# NMEA-v8-iso.net
KiCad netlist of a schematic drawn in EAGLE
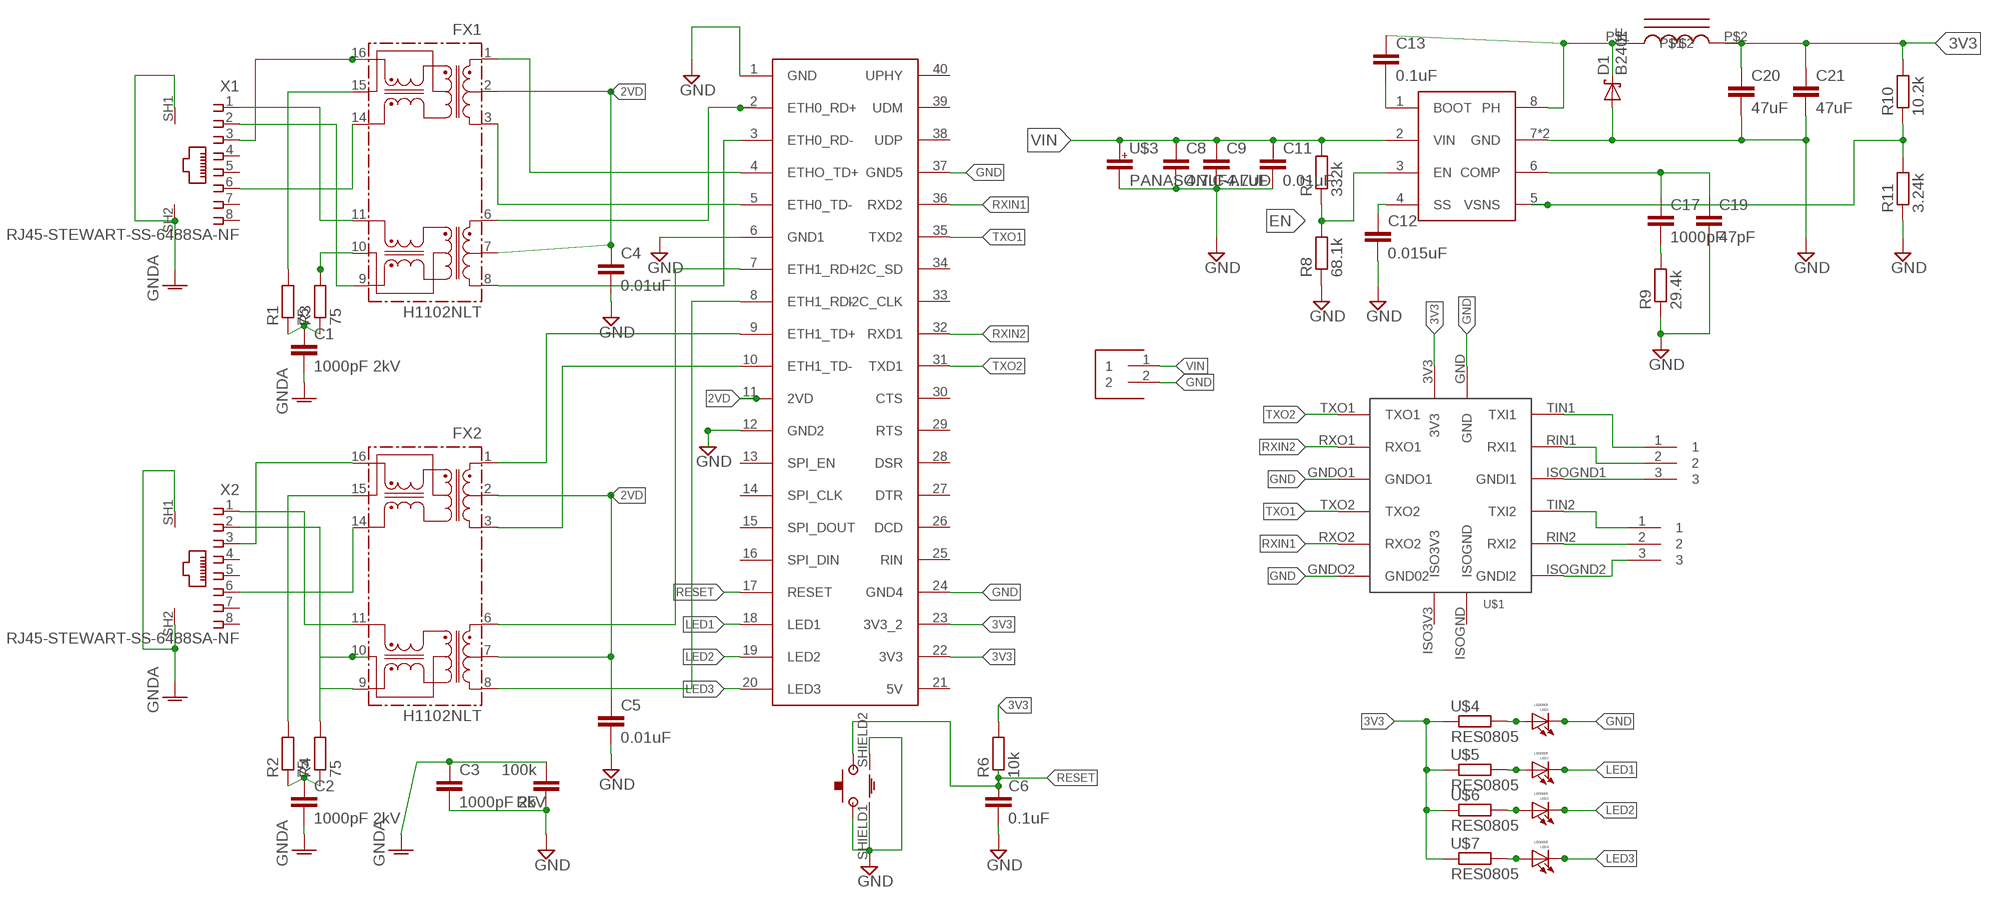
[diagram p0: schematic, sheet 1]

(export (version "E")
  (design (tool "Eeschema 10.0.6"))
  (components
    (comp (ref "C1")
      (value "1000pF 2kV")
      (footprint "eagle-import:1206")
      (libsource (lib "eagle-import") (part "CAP1206"))
    )
    (comp (ref "C2")
      (value "1000pF 2kV")
      (footprint "eagle-import:1206")
      (libsource (lib "eagle-import") (part "CAP1206"))
    )
    (comp (ref "C3")
      (value "1000pF 2kV")
      (footprint "eagle-import:1206")
      (libsource (lib "eagle-import") (part "CAP1206"))
    )
    (comp (ref "C4")
      (value "0.01uF")
      (footprint "eagle-import:0805")
      (libsource (lib "eagle-import") (part "CAP0805"))
    )
    (comp (ref "C5")
      (value "0.01uF")
      (footprint "eagle-import:0805")
      (libsource (lib "eagle-import") (part "CAP0805"))
    )
    (comp (ref "C6")
      (value "0.1uF")
      (footprint "eagle-import:0805")
      (libsource (lib "eagle-import") (part "CAP0805"))
    )
    (comp (ref "C8")
      (value "4.7uF")
      (footprint "eagle-import:1210")
      (libsource (lib "eagle-import") (part "CAP1210"))
    )
    (comp (ref "C9")
      (value "4.7uF")
      (footprint "eagle-import:1210")
      (libsource (lib "eagle-import") (part "CAP1210"))
    )
    (comp (ref "C11")
      (value "0.01uF")
      (footprint "eagle-import:0805")
      (libsource (lib "eagle-import") (part "CAP0805"))
    )
    (comp (ref "C12")
      (value "0.015uF")
      (footprint "eagle-import:0805")
      (libsource (lib "eagle-import") (part "CAP0805"))
    )
    (comp (ref "C13")
      (value "0.1uF")
      (footprint "eagle-import:0805")
      (libsource (lib "eagle-import") (part "CAP0805"))
    )
    (comp (ref "C17")
      (value "1000pF")
      (footprint "eagle-import:0805")
      (libsource (lib "eagle-import") (part "CAP0805"))
    )
    (comp (ref "C19")
      (value "47pF")
      (footprint "eagle-import:0805")
      (libsource (lib "eagle-import") (part "CAP0805"))
    )
    (comp (ref "C20")
      (value "47uF")
      (footprint "eagle-import:1206")
      (libsource (lib "eagle-import") (part "CAP1206"))
    )
    (comp (ref "C21")
      (value "47uF")
      (footprint "eagle-import:1206")
      (libsource (lib "eagle-import") (part "CAP1206"))
    )
    (comp (ref "CARAMBOLA")
      (value "CARAMBOLA")
      (footprint "eagle-import:CARAMBOLA")
      (libsource (lib "eagle-import") (part "CARAMBOLA"))
    )
    (comp (ref "D1")
      (value "B240F")
      (footprint "eagle-import:SMB")
      (libsource (lib "eagle-import") (part "B240F"))
    )
    (comp (ref "DATA1")
      (value "CON-3")
      (footprint "eagle-import:CON-3")
      (libsource (lib "eagle-import") (part "CON-3"))
    )
    (comp (ref "DATA2")
      (value "CON-3")
      (footprint "eagle-import:CON-3")
      (libsource (lib "eagle-import") (part "CON-3"))
    )
    (comp (ref "FX1")
      (value "H1102NLT")
      (footprint "eagle-import:H_HX1XXXNL")
      (libsource (lib "eagle-import") (part "H1102NLT"))
    )
    (comp (ref "FX2")
      (value "H1102NLT")
      (footprint "eagle-import:H_HX1XXXNL")
      (libsource (lib "eagle-import") (part "H1102NLT"))
    )
    (comp (ref "J1")
      (value "CON-5MM-2")
      (footprint "eagle-import:CON--5MM-2")
      (libsource (lib "eagle-import") (part "CON-5MM-2"))
    )
    (comp (ref "L1")
      (value "CLF_TDK_INDUCTORCLF10040")
      (footprint "eagle-import:CLF10040")
      (libsource (lib "eagle-import") (part "CLF_TDK_INDUCTORCLF10040"))
    )
    (comp (ref "LED1")
      (value "LED0805")
      (footprint "eagle-import:L0805")
      (libsource (lib "eagle-import") (part "LED0805"))
    )
    (comp (ref "LED2")
      (value "LED0805")
      (footprint "eagle-import:L0805")
      (libsource (lib "eagle-import") (part "LED0805"))
    )
    (comp (ref "LED3")
      (value "LED0805")
      (footprint "eagle-import:L0805")
      (libsource (lib "eagle-import") (part "LED0805"))
    )
    (comp (ref "LED4")
      (value "LED0805")
      (footprint "eagle-import:L0805")
      (libsource (lib "eagle-import") (part "LED0805"))
    )
    (comp (ref "R1")
      (value "75")
      (footprint "eagle-import:0805")
      (libsource (lib "eagle-import") (part "RES0805"))
    )
    (comp (ref "R2")
      (value "75")
      (footprint "eagle-import:0805")
      (libsource (lib "eagle-import") (part "RES0805"))
    )
    (comp (ref "R3")
      (value "75")
      (footprint "eagle-import:0805")
      (libsource (lib "eagle-import") (part "RES0805"))
    )
    (comp (ref "R4")
      (value "75")
      (footprint "eagle-import:0805")
      (libsource (lib "eagle-import") (part "RES0805"))
    )
    (comp (ref "R5")
      (value "100k")
      (footprint "eagle-import:1206")
      (libsource (lib "eagle-import") (part "CAP1206"))
    )
    (comp (ref "R6")
      (value "10k")
      (footprint "eagle-import:0805")
      (libsource (lib "eagle-import") (part "RES0805"))
    )
    (comp (ref "R7")
      (value "332k")
      (footprint "eagle-import:0805")
      (libsource (lib "eagle-import") (part "RES0805"))
    )
    (comp (ref "R8")
      (value "68.1k")
      (footprint "eagle-import:0805")
      (libsource (lib "eagle-import") (part "RES0805"))
    )
    (comp (ref "R9")
      (value "29.4k")
      (footprint "eagle-import:0805")
      (libsource (lib "eagle-import") (part "RES0805"))
    )
    (comp (ref "R10")
      (value "10.2k")
      (footprint "eagle-import:0805")
      (libsource (lib "eagle-import") (part "RES0805"))
    )
    (comp (ref "R11")
      (value "3.24k")
      (footprint "eagle-import:0805")
      (libsource (lib "eagle-import") (part "RES0805"))
    )
    (comp (ref "U$1")
      (value "ISO-BOARD")
      (footprint "eagle-import:ISO-BOARD")
      (libsource (lib "eagle-import") (part "ISO-BOARD"))
    )
    (comp (ref "U$2")
      (value "TACTILE-SWITCH-FSMRA1J")
      (footprint "eagle-import:TACTILE-SWITCH-FSMRA1J")
      (libsource (lib "eagle-import") (part "TACTILE-SWITCH-FSMRA1J"))
    )
    (comp (ref "U$3")
      (value "PANASONIC-ALUD")
      (footprint "eagle-import:PANASONIC_D")
      (libsource (lib "eagle-import") (part "PANASONIC-ALUD"))
    )
    (comp (ref "U$4")
      (value "RES0805")
      (footprint "eagle-import:0805")
      (libsource (lib "eagle-import") (part "RES0805"))
    )
    (comp (ref "U$5")
      (value "RES0805")
      (footprint "eagle-import:0805")
      (libsource (lib "eagle-import") (part "RES0805"))
    )
    (comp (ref "U$6")
      (value "RES0805")
      (footprint "eagle-import:0805")
      (libsource (lib "eagle-import") (part "RES0805"))
    )
    (comp (ref "U$7")
      (value "RES0805")
      (footprint "eagle-import:0805")
      (libsource (lib "eagle-import") (part "RES0805"))
    )
    (comp (ref "U8")
      (value "TPS54231")
      (footprint "eagle-import:SOIC-THERMAL")
      (libsource (lib "eagle-import") (part "TPS54231"))
    )
    (comp (ref "X1")
      (value "RJ45-STEWART-SS-6488SA-NF")
      (footprint "eagle-import:RJ45-STEWART-6488")
      (libsource (lib "eagle-import") (part "RJ45-STEWART-SS-6488SA-NF"))
    )
    (comp (ref "X2")
      (value "RJ45-STEWART-SS-6488SA-NF")
      (footprint "eagle-import:RJ45-STEWART-6488")
      (libsource (lib "eagle-import") (part "RJ45-STEWART-SS-6488SA-NF"))
    )
  )
  (nets
    (net (code "1") (name "2VD") (class "Default")
      (node (ref "C4") (pin "1") (pinfunction "1_1") (pintype "passive"))
      (node (ref "C5") (pin "1") (pinfunction "1_1") (pintype "passive"))
      (node (ref "CARAMBOLA") (pin "11") (pinfunction "2VD_11") (pintype "bidirectional"))
      (node (ref "FX1") (pin "2") (pinfunction "2_2") (pintype "passive"))
      (node (ref "FX1") (pin "7") (pinfunction "7_7") (pintype "passive"))
      (node (ref "FX2") (pin "2") (pinfunction "2_2") (pintype "passive"))
      (node (ref "FX2") (pin "7") (pinfunction "7_7") (pintype "passive"))
    )
    (net (code "2") (name "3V3") (class "Default")
      (node (ref "C20") (pin "1") (pinfunction "1_1") (pintype "passive"))
      (node (ref "C21") (pin "1") (pinfunction "1_1") (pintype "passive"))
      (node (ref "CARAMBOLA") (pin "22") (pinfunction "3V3_22") (pintype "bidirectional"))
      (node (ref "CARAMBOLA") (pin "23") (pinfunction "3V3_2_23") (pintype "bidirectional"))
      (node (ref "L1") (pin "P$2") (pinfunction "P$2_P$2") (pintype "bidirectional"))
      (node (ref "R10") (pin "2") (pinfunction "2_2") (pintype "passive"))
      (node (ref "R6") (pin "2") (pinfunction "2_2") (pintype "passive"))
      (node (ref "U$1") (pin "3V3") (pinfunction "3V3_3V3") (pintype "bidirectional"))
      (node (ref "U$4") (pin "1") (pinfunction "1_1") (pintype "passive"))
      (node (ref "U$5") (pin "1") (pinfunction "1_1") (pintype "passive"))
      (node (ref "U$6") (pin "1") (pinfunction "1_1") (pintype "passive"))
      (node (ref "U$7") (pin "1") (pinfunction "1_1") (pintype "passive"))
    )
    (net (code "3") (name "EN") (class "Default")
      (node (ref "R7") (pin "1") (pinfunction "1_1") (pintype "passive"))
      (node (ref "R8") (pin "2") (pinfunction "2_2") (pintype "passive"))
      (node (ref "U8") (pin "3") (pinfunction "EN_3") (pintype "bidirectional"))
    )
    (net (code "4") (name "GND") (class "Default")
      (node (ref "C11") (pin "2") (pinfunction "2_2") (pintype "passive"))
      (node (ref "C12") (pin "2") (pinfunction "2_2") (pintype "passive"))
      (node (ref "C19") (pin "2") (pinfunction "2_2") (pintype "passive"))
      (node (ref "C20") (pin "2") (pinfunction "2_2") (pintype "passive"))
      (node (ref "C21") (pin "2") (pinfunction "2_2") (pintype "passive"))
      (node (ref "C3") (pin "2") (pinfunction "2_2") (pintype "passive"))
      (node (ref "C4") (pin "2") (pinfunction "2_2") (pintype "passive"))
      (node (ref "C5") (pin "2") (pinfunction "2_2") (pintype "passive"))
      (node (ref "C6") (pin "2") (pinfunction "2_2") (pintype "passive"))
      (node (ref "C8") (pin "2") (pinfunction "2_2") (pintype "passive"))
      (node (ref "C9") (pin "2") (pinfunction "2_2") (pintype "passive"))
      (node (ref "CARAMBOLA") (pin "1") (pinfunction "GND_1") (pintype "bidirectional"))
      (node (ref "CARAMBOLA") (pin "12") (pinfunction "GND2_12") (pintype "bidirectional"))
      (node (ref "CARAMBOLA") (pin "24") (pinfunction "GND4_24") (pintype "bidirectional"))
      (node (ref "CARAMBOLA") (pin "37") (pinfunction "GND5_37") (pintype "bidirectional"))
      (node (ref "CARAMBOLA") (pin "6") (pinfunction "GND1_6") (pintype "bidirectional"))
      (node (ref "D1") (pin "A") (pinfunction "A_A") (pintype "passive"))
      (node (ref "J1") (pin "2") (pinfunction "2_2") (pintype "bidirectional"))
      (node (ref "LED1") (pin "C") (pinfunction "C_C") (pintype "passive"))
      (node (ref "R11") (pin "1") (pinfunction "1_1") (pintype "passive"))
      (node (ref "R5") (pin "1") (pinfunction "1_1") (pintype "passive"))
      (node (ref "R8") (pin "1") (pinfunction "1_1") (pintype "passive"))
      (node (ref "R9") (pin "1") (pinfunction "1_1") (pintype "passive"))
      (node (ref "U$1") (pin "GND") (pinfunction "GND_GND") (pintype "bidirectional"))
      (node (ref "U$1") (pin "GNDO1") (pinfunction "GNDO1_GNDO1") (pintype "bidirectional"))
      (node (ref "U$1") (pin "GNDO2") (pinfunction "GND02_GNDO2") (pintype "bidirectional"))
      (node (ref "U$2") (pin "2") (pinfunction "2_2") (pintype "bidirectional"))
      (node (ref "U$2") (pin "SHIELD1") (pinfunction "SHIELD1_SHIELD1") (pintype "bidirectional"))
      (node (ref "U$2") (pin "SHIELD2") (pinfunction "SHIELD2_SHIELD2") (pintype "bidirectional"))
      (node (ref "U$3") (pin "-") (pinfunction "-_-") (pintype "passive"))
      (node (ref "U8") (pin "7") (pinfunction "GND_7") (pintype "bidirectional"))
      (node (ref "U8") (pin "P$1") (pinfunction "GND_P$1") (pintype "bidirectional"))
    )
    (net (code "5") (name "GNDA") (class "Default")
      (node (ref "C1") (pin "2") (pinfunction "2_2") (pintype "passive"))
      (node (ref "C2") (pin "2") (pinfunction "2_2") (pintype "passive"))
      (node (ref "C3") (pin "1") (pinfunction "1_1") (pintype "passive"))
      (node (ref "R5") (pin "2") (pinfunction "2_2") (pintype "passive"))
      (node (ref "X1") (pin "SH1") (pinfunction "SH1_SH1") (pintype "bidirectional"))
      (node (ref "X1") (pin "SH2") (pinfunction "SH2_SH2") (pintype "bidirectional"))
      (node (ref "X2") (pin "SH1") (pinfunction "SH1_SH1") (pintype "bidirectional"))
      (node (ref "X2") (pin "SH2") (pinfunction "SH2_SH2") (pintype "bidirectional"))
    )
    (net (code "6") (name "LED1") (class "Default")
      (node (ref "CARAMBOLA") (pin "18") (pinfunction "LED1_18") (pintype "bidirectional"))
      (node (ref "LED2") (pin "C") (pinfunction "C_C") (pintype "passive"))
    )
    (net (code "7") (name "LED2") (class "Default")
      (node (ref "CARAMBOLA") (pin "19") (pinfunction "LED2_19") (pintype "bidirectional"))
      (node (ref "LED3") (pin "C") (pinfunction "C_C") (pintype "passive"))
    )
    (net (code "8") (name "LED3") (class "Default")
      (node (ref "CARAMBOLA") (pin "20") (pinfunction "LED3_20") (pintype "bidirectional"))
      (node (ref "LED4") (pin "C") (pinfunction "C_C") (pintype "passive"))
    )
    (net (code "9") (name "Net-(C1-Pad1)") (class "Default")
      (node (ref "C1") (pin "1") (pinfunction "1_1") (pintype "passive"))
      (node (ref "R1") (pin "1") (pinfunction "1_1") (pintype "passive"))
      (node (ref "R3") (pin "1") (pinfunction "1_1") (pintype "passive"))
    )
    (net (code "10") (name "Net-(C2-Pad1)") (class "Default")
      (node (ref "C2") (pin "1") (pinfunction "1_1") (pintype "passive"))
      (node (ref "R2") (pin "1") (pinfunction "1_1") (pintype "passive"))
      (node (ref "R4") (pin "1") (pinfunction "1_1") (pintype "passive"))
    )
    (net (code "11") (name "Net-(C17-Pad2)") (class "Default")
      (node (ref "C17") (pin "2") (pinfunction "2_2") (pintype "passive"))
      (node (ref "R9") (pin "2") (pinfunction "2_2") (pintype "passive"))
    )
    (net (code "12") (name "Net-(CARAMBOLA-ETH0_RD+)") (class "Default")
      (node (ref "CARAMBOLA") (pin "2") (pinfunction "ETH0_RD+_2") (pintype "bidirectional"))
      (node (ref "FX1") (pin "6") (pinfunction "6_6") (pintype "passive"))
    )
    (net (code "13") (name "Net-(CARAMBOLA-ETH0_RD-)") (class "Default")
      (node (ref "CARAMBOLA") (pin "3") (pinfunction "ETH0_RD-_3") (pintype "bidirectional"))
      (node (ref "FX1") (pin "8") (pinfunction "8_8") (pintype "passive"))
    )
    (net (code "14") (name "Net-(CARAMBOLA-ETH0_TD-)") (class "Default")
      (node (ref "CARAMBOLA") (pin "5") (pinfunction "ETH0_TD-_5") (pintype "bidirectional"))
      (node (ref "FX1") (pin "3") (pinfunction "3_3") (pintype "passive"))
    )
    (net (code "15") (name "Net-(CARAMBOLA-ETH1_RD+)") (class "Default")
      (node (ref "CARAMBOLA") (pin "7") (pinfunction "ETH1_RD+_7") (pintype "bidirectional"))
      (node (ref "FX2") (pin "6") (pinfunction "6_6") (pintype "passive"))
    )
    (net (code "16") (name "Net-(CARAMBOLA-ETH1_RD-)") (class "Default")
      (node (ref "CARAMBOLA") (pin "8") (pinfunction "ETH1_RD-_8") (pintype "bidirectional"))
      (node (ref "FX2") (pin "8") (pinfunction "8_8") (pintype "passive"))
    )
    (net (code "17") (name "Net-(CARAMBOLA-ETH1_TD+)") (class "Default")
      (node (ref "CARAMBOLA") (pin "9") (pinfunction "ETH1_TD+_9") (pintype "bidirectional"))
      (node (ref "FX2") (pin "1") (pinfunction "1_1") (pintype "passive"))
    )
    (net (code "18") (name "Net-(CARAMBOLA-ETH1_TD-)") (class "Default")
      (node (ref "CARAMBOLA") (pin "10") (pinfunction "ETH1_TD-_10") (pintype "bidirectional"))
      (node (ref "FX2") (pin "3") (pinfunction "3_3") (pintype "passive"))
    )
    (net (code "19") (name "Net-(CARAMBOLA-ETHO_TD+)") (class "Default")
      (node (ref "CARAMBOLA") (pin "4") (pinfunction "ETHO_TD+_4") (pintype "bidirectional"))
      (node (ref "FX1") (pin "1") (pinfunction "1_1") (pintype "passive"))
    )
    (net (code "20") (name "Net-(FX1-Pad9)") (class "Default")
      (node (ref "FX1") (pin "9") (pinfunction "9_9") (pintype "passive"))
      (node (ref "X1") (pin "2") (pinfunction "2_2") (pintype "passive"))
    )
    (net (code "21") (name "Net-(FX1-Pad10)") (class "Default")
      (node (ref "FX1") (pin "10") (pinfunction "10_10") (pintype "passive"))
      (node (ref "R3") (pin "2") (pinfunction "2_2") (pintype "passive"))
    )
    (net (code "22") (name "Net-(FX1-Pad11)") (class "Default")
      (node (ref "FX1") (pin "11") (pinfunction "11_11") (pintype "passive"))
      (node (ref "X1") (pin "1") (pinfunction "1_1") (pintype "passive"))
    )
    (net (code "23") (name "Net-(FX1-Pad14)") (class "Default")
      (node (ref "FX1") (pin "14") (pinfunction "14_14") (pintype "passive"))
      (node (ref "X1") (pin "6") (pinfunction "6_6") (pintype "passive"))
    )
    (net (code "24") (name "Net-(FX1-Pad15)") (class "Default")
      (node (ref "FX1") (pin "15") (pinfunction "15_15") (pintype "passive"))
      (node (ref "R1") (pin "2") (pinfunction "2_2") (pintype "passive"))
    )
    (net (code "25") (name "Net-(FX1-Pad16)") (class "Default")
      (node (ref "FX1") (pin "16") (pinfunction "16_16") (pintype "passive"))
      (node (ref "X1") (pin "3") (pinfunction "3_3") (pintype "passive"))
    )
    (net (code "26") (name "Net-(FX2-Pad9)") (class "Default")
      (node (ref "FX2") (pin "9") (pinfunction "9_9") (pintype "passive"))
      (node (ref "X2") (pin "2") (pinfunction "2_2") (pintype "passive"))
    )
    (net (code "27") (name "Net-(FX2-Pad10)") (class "Default")
      (node (ref "FX2") (pin "10") (pinfunction "10_10") (pintype "passive"))
      (node (ref "R4") (pin "2") (pinfunction "2_2") (pintype "passive"))
    )
    (net (code "28") (name "Net-(FX2-Pad11)") (class "Default")
      (node (ref "FX2") (pin "11") (pinfunction "11_11") (pintype "passive"))
      (node (ref "X2") (pin "1") (pinfunction "1_1") (pintype "passive"))
    )
    (net (code "29") (name "Net-(FX2-Pad14)") (class "Default")
      (node (ref "FX2") (pin "14") (pinfunction "14_14") (pintype "passive"))
      (node (ref "X2") (pin "6") (pinfunction "6_6") (pintype "passive"))
    )
    (net (code "30") (name "Net-(FX2-Pad15)") (class "Default")
      (node (ref "FX2") (pin "15") (pinfunction "15_15") (pintype "passive"))
      (node (ref "R2") (pin "2") (pinfunction "2_2") (pintype "passive"))
    )
    (net (code "31") (name "Net-(FX2-Pad16)") (class "Default")
      (node (ref "FX2") (pin "16") (pinfunction "16_16") (pintype "passive"))
      (node (ref "X2") (pin "3") (pinfunction "3_3") (pintype "passive"))
    )
    (net (code "32") (name "Net-(LED1-PadA)") (class "Default")
      (node (ref "LED1") (pin "A") (pinfunction "A_A") (pintype "passive"))
      (node (ref "U$4") (pin "2") (pinfunction "2_2") (pintype "passive"))
    )
    (net (code "33") (name "Net-(LED2-PadA)") (class "Default")
      (node (ref "LED2") (pin "A") (pinfunction "A_A") (pintype "passive"))
      (node (ref "U$5") (pin "2") (pinfunction "2_2") (pintype "passive"))
    )
    (net (code "34") (name "Net-(LED3-PadA)") (class "Default")
      (node (ref "LED3") (pin "A") (pinfunction "A_A") (pintype "passive"))
      (node (ref "U$6") (pin "2") (pinfunction "2_2") (pintype "passive"))
    )
    (net (code "35") (name "Net-(LED4-PadA)") (class "Default")
      (node (ref "LED4") (pin "A") (pinfunction "A_A") (pintype "passive"))
      (node (ref "U$7") (pin "2") (pinfunction "2_2") (pintype "passive"))
    )
    (net (code "36") (name "Net-(U$1-GNDI1)") (class "Default")
      (node (ref "DATA1") (pin "3") (pinfunction "3_3") (pintype "bidirectional"))
      (node (ref "U$1") (pin "ISOGND1") (pinfunction "GNDI1_ISOGND1") (pintype "bidirectional"))
    )
    (net (code "37") (name "Net-(U$1-GNDI2)") (class "Default")
      (node (ref "DATA2") (pin "3") (pinfunction "3_3") (pintype "bidirectional"))
      (node (ref "U$1") (pin "ISOGND2") (pinfunction "GNDI2_ISOGND2") (pintype "bidirectional"))
    )
    (net (code "38") (name "Net-(U$1-RXI1)") (class "Default")
      (node (ref "DATA1") (pin "2") (pinfunction "2_2") (pintype "bidirectional"))
      (node (ref "U$1") (pin "RIN1") (pinfunction "RXI1_RIN1") (pintype "bidirectional"))
    )
    (net (code "39") (name "Net-(U$1-RXI2)") (class "Default")
      (node (ref "DATA2") (pin "2") (pinfunction "2_2") (pintype "bidirectional"))
      (node (ref "U$1") (pin "RIN2") (pinfunction "RXI2_RIN2") (pintype "bidirectional"))
    )
    (net (code "40") (name "Net-(U$1-TXI1)") (class "Default")
      (node (ref "DATA1") (pin "1") (pinfunction "1_1") (pintype "bidirectional"))
      (node (ref "U$1") (pin "TIN1") (pinfunction "TXI1_TIN1") (pintype "bidirectional"))
    )
    (net (code "41") (name "Net-(U$1-TXI2)") (class "Default")
      (node (ref "DATA2") (pin "1") (pinfunction "1_1") (pintype "bidirectional"))
      (node (ref "U$1") (pin "TIN2") (pinfunction "TXI2_TIN2") (pintype "bidirectional"))
    )
    (net (code "42") (name "Net-(U8-BOOT)") (class "Default")
      (node (ref "C13") (pin "2") (pinfunction "2_2") (pintype "passive"))
      (node (ref "U8") (pin "1") (pinfunction "BOOT_1") (pintype "bidirectional"))
    )
    (net (code "43") (name "Net-(U8-COMP)") (class "Default")
      (node (ref "C17") (pin "1") (pinfunction "1_1") (pintype "passive"))
      (node (ref "C19") (pin "1") (pinfunction "1_1") (pintype "passive"))
      (node (ref "U8") (pin "6") (pinfunction "COMP_6") (pintype "bidirectional"))
    )
    (net (code "44") (name "Net-(U8-PH)") (class "Default")
      (node (ref "C13") (pin "1") (pinfunction "1_1") (pintype "passive"))
      (node (ref "D1") (pin "C") (pinfunction "C_C") (pintype "passive"))
      (node (ref "L1") (pin "P$1") (pinfunction "P$1_P$1") (pintype "bidirectional"))
      (node (ref "U8") (pin "8") (pinfunction "PH_8") (pintype "bidirectional"))
    )
    (net (code "45") (name "Net-(U8-SS)") (class "Default")
      (node (ref "C12") (pin "1") (pinfunction "1_1") (pintype "passive"))
      (node (ref "U8") (pin "4") (pinfunction "SS_4") (pintype "bidirectional"))
    )
    (net (code "46") (name "Net-(U8-VSNS)") (class "Default")
      (node (ref "R10") (pin "1") (pinfunction "1_1") (pintype "passive"))
      (node (ref "R11") (pin "2") (pinfunction "2_2") (pintype "passive"))
      (node (ref "U8") (pin "5") (pinfunction "VSNS_5") (pintype "bidirectional"))
    )
    (net (code "47") (name "RESET") (class "Default")
      (node (ref "C6") (pin "1") (pinfunction "1_1") (pintype "passive"))
      (node (ref "CARAMBOLA") (pin "17") (pinfunction "RESET_17") (pintype "bidirectional"))
      (node (ref "R6") (pin "1") (pinfunction "1_1") (pintype "passive"))
      (node (ref "U$2") (pin "1") (pinfunction "1_1") (pintype "bidirectional"))
    )
    (net (code "48") (name "RXIN1") (class "Default")
      (node (ref "CARAMBOLA") (pin "36") (pinfunction "RXD2_36") (pintype "bidirectional"))
      (node (ref "U$1") (pin "RXO2") (pinfunction "RXO2_RXO2") (pintype "bidirectional"))
    )
    (net (code "49") (name "RXIN2") (class "Default")
      (node (ref "CARAMBOLA") (pin "32") (pinfunction "RXD1_32") (pintype "bidirectional"))
      (node (ref "U$1") (pin "RXO1") (pinfunction "RXO1_RXO1") (pintype "bidirectional"))
    )
    (net (code "50") (name "TXO1") (class "Default")
      (node (ref "CARAMBOLA") (pin "35") (pinfunction "TXD2_35") (pintype "bidirectional"))
      (node (ref "U$1") (pin "TXO2") (pinfunction "TXO2_TXO2") (pintype "bidirectional"))
    )
    (net (code "51") (name "TXO2") (class "Default")
      (node (ref "CARAMBOLA") (pin "31") (pinfunction "TXD1_31") (pintype "bidirectional"))
      (node (ref "U$1") (pin "TXO1") (pinfunction "TXO1_TXO1") (pintype "bidirectional"))
    )
    (net (code "52") (name "VIN") (class "Default")
      (node (ref "C11") (pin "1") (pinfunction "1_1") (pintype "passive"))
      (node (ref "C8") (pin "1") (pinfunction "1_1") (pintype "passive"))
      (node (ref "C9") (pin "1") (pinfunction "1_1") (pintype "passive"))
      (node (ref "J1") (pin "1") (pinfunction "1_1") (pintype "bidirectional"))
      (node (ref "R7") (pin "2") (pinfunction "2_2") (pintype "passive"))
      (node (ref "U$3") (pin "+") (pinfunction "+_+") (pintype "passive"))
      (node (ref "U8") (pin "2") (pinfunction "VIN_2") (pintype "bidirectional"))
    )
    (net (code "53") (name "unconnected-(CARAMBOLA-5V-Pad21)") (class "Default")
      (node (ref "CARAMBOLA") (pin "21") (pinfunction "5V_21") (pintype "bidirectional"))
    )
    (net (code "54") (name "unconnected-(CARAMBOLA-CTS-Pad30)") (class "Default")
      (node (ref "CARAMBOLA") (pin "30") (pinfunction "CTS_30") (pintype "bidirectional"))
    )
    (net (code "55") (name "unconnected-(CARAMBOLA-DCD-Pad26)") (class "Default")
      (node (ref "CARAMBOLA") (pin "26") (pinfunction "DCD_26") (pintype "bidirectional"))
    )
    (net (code "56") (name "unconnected-(CARAMBOLA-DSR-Pad28)") (class "Default")
      (node (ref "CARAMBOLA") (pin "28") (pinfunction "DSR_28") (pintype "bidirectional"))
    )
    (net (code "57") (name "unconnected-(CARAMBOLA-DTR-Pad27)") (class "Default")
      (node (ref "CARAMBOLA") (pin "27") (pinfunction "DTR_27") (pintype "bidirectional"))
    )
    (net (code "58") (name "unconnected-(CARAMBOLA-I2C_CLK-Pad33)") (class "Default")
      (node (ref "CARAMBOLA") (pin "33") (pinfunction "I2C_CLK_33") (pintype "bidirectional"))
    )
    (net (code "59") (name "unconnected-(CARAMBOLA-I2C_SD-Pad34)") (class "Default")
      (node (ref "CARAMBOLA") (pin "34") (pinfunction "I2C_SD_34") (pintype "bidirectional"))
    )
    (net (code "60") (name "unconnected-(CARAMBOLA-RIN-Pad25)") (class "Default")
      (node (ref "CARAMBOLA") (pin "25") (pinfunction "RIN_25") (pintype "bidirectional"))
    )
    (net (code "61") (name "unconnected-(CARAMBOLA-RTS-Pad29)") (class "Default")
      (node (ref "CARAMBOLA") (pin "29") (pinfunction "RTS_29") (pintype "bidirectional"))
    )
    (net (code "62") (name "unconnected-(CARAMBOLA-SPI_CLK-Pad14)") (class "Default")
      (node (ref "CARAMBOLA") (pin "14") (pinfunction "SPI_CLK_14") (pintype "bidirectional"))
    )
    (net (code "63") (name "unconnected-(CARAMBOLA-SPI_DIN-Pad16)") (class "Default")
      (node (ref "CARAMBOLA") (pin "16") (pinfunction "SPI_DIN_16") (pintype "bidirectional"))
    )
    (net (code "64") (name "unconnected-(CARAMBOLA-SPI_DOUT-Pad15)") (class "Default")
      (node (ref "CARAMBOLA") (pin "15") (pinfunction "SPI_DOUT_15") (pintype "bidirectional"))
    )
    (net (code "65") (name "unconnected-(CARAMBOLA-SPI_EN-Pad13)") (class "Default")
      (node (ref "CARAMBOLA") (pin "13") (pinfunction "SPI_EN_13") (pintype "bidirectional"))
    )
    (net (code "66") (name "unconnected-(CARAMBOLA-UDM-Pad39)") (class "Default")
      (node (ref "CARAMBOLA") (pin "39") (pinfunction "UDM_39") (pintype "bidirectional"))
    )
    (net (code "67") (name "unconnected-(CARAMBOLA-UDP-Pad38)") (class "Default")
      (node (ref "CARAMBOLA") (pin "38") (pinfunction "UDP_38") (pintype "bidirectional"))
    )
    (net (code "68") (name "unconnected-(CARAMBOLA-UPHY-Pad40)") (class "Default")
      (node (ref "CARAMBOLA") (pin "40") (pinfunction "UPHY_40") (pintype "bidirectional"))
    )
    (net (code "69") (name "unconnected-(U$1-PadISO3V3)") (class "Default")
      (node (ref "U$1") (pin "ISO3V3") (pinfunction "ISO3V3_ISO3V3") (pintype "bidirectional"))
    )
    (net (code "70") (name "unconnected-(U$1-PadISOGND)") (class "Default")
      (node (ref "U$1") (pin "ISOGND") (pinfunction "ISOGND_ISOGND") (pintype "bidirectional"))
    )
    (net (code "71") (name "unconnected-(X1-Pad4)") (class "Default")
      (node (ref "X1") (pin "4") (pinfunction "4_4") (pintype "passive"))
    )
    (net (code "72") (name "unconnected-(X1-Pad5)") (class "Default")
      (node (ref "X1") (pin "5") (pinfunction "5_5") (pintype "passive"))
    )
    (net (code "73") (name "unconnected-(X1-Pad7)") (class "Default")
      (node (ref "X1") (pin "7") (pinfunction "7_7") (pintype "passive"))
    )
    (net (code "74") (name "unconnected-(X1-Pad8)") (class "Default")
      (node (ref "X1") (pin "8") (pinfunction "8_8") (pintype "passive"))
    )
    (net (code "75") (name "unconnected-(X2-Pad4)") (class "Default")
      (node (ref "X2") (pin "4") (pinfunction "4_4") (pintype "passive"))
    )
    (net (code "76") (name "unconnected-(X2-Pad5)") (class "Default")
      (node (ref "X2") (pin "5") (pinfunction "5_5") (pintype "passive"))
    )
    (net (code "77") (name "unconnected-(X2-Pad7)") (class "Default")
      (node (ref "X2") (pin "7") (pinfunction "7_7") (pintype "passive"))
    )
    (net (code "78") (name "unconnected-(X2-Pad8)") (class "Default")
      (node (ref "X2") (pin "8") (pinfunction "8_8") (pintype "passive"))
    )
  )
)
